# SparkFun_Breadboard_Power_Supply_5_3_3V.net
KiCad netlist of a schematic drawn in EAGLE
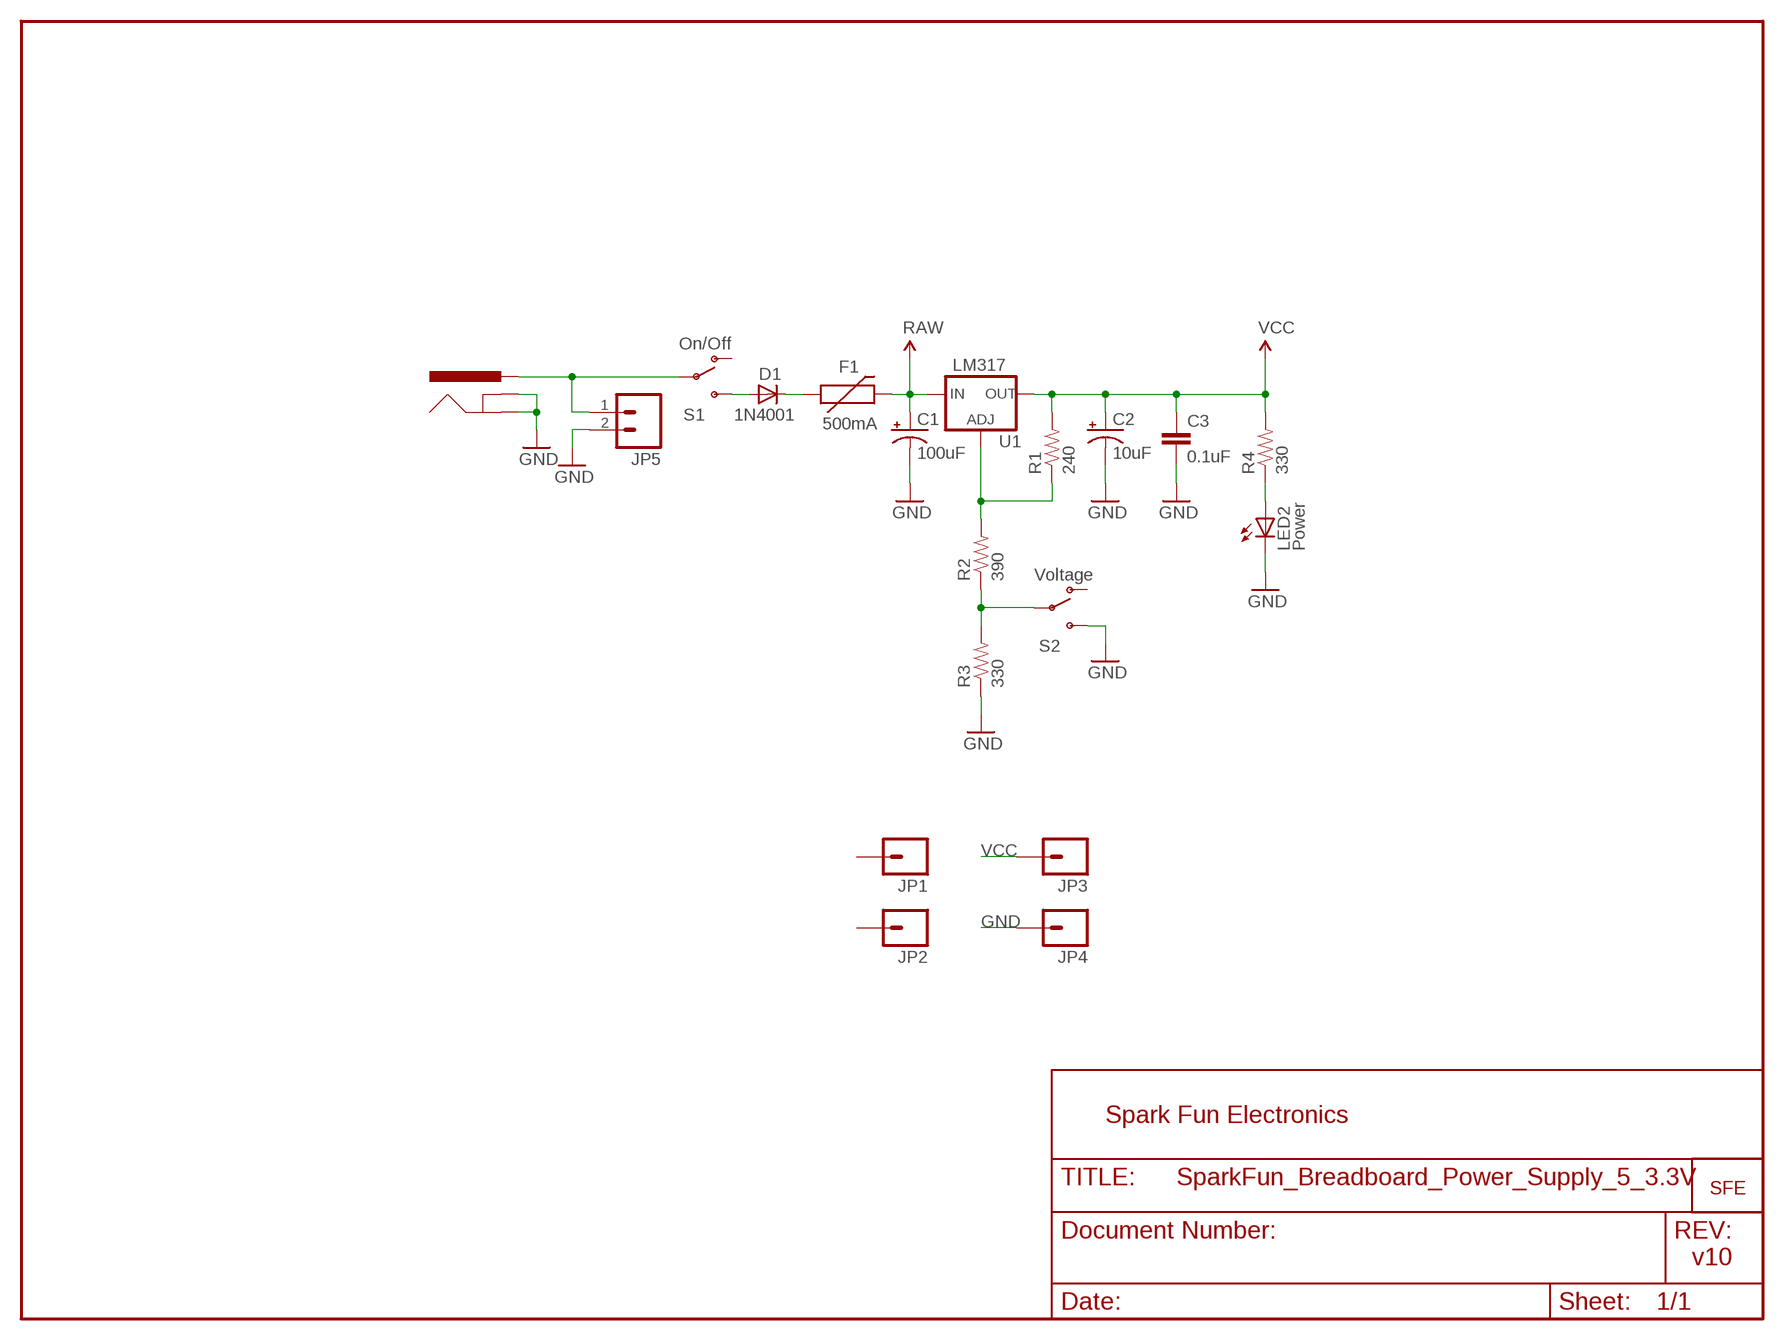
[diagram p0: schematic, sheet 1]

(export (version "E")
  (design (tool "Eeschema 10.0.6"))
  (components
    (comp (ref "C1")
      (value "100uF")
      (footprint "eagle-import:CPOL-RADIAL-100UF-25V")
      (libsource (lib "eagle-import") (part "CAP_POLPTH1"))
    )
    (comp (ref "C2")
      (value "10uF")
      (footprint "eagle-import:CPOL-RADIAL-10UF-25V")
      (libsource (lib "eagle-import") (part "CAP_POLPTH2"))
    )
    (comp (ref "C3")
      (value "0.1uF")
      (footprint "eagle-import:CAP-PTH-SMALL2")
      (libsource (lib "eagle-import") (part "CAPPTH2"))
    )
    (comp (ref "D1")
      (value "1N4001")
      (footprint "eagle-import:DIODE-0.4")
      (libsource (lib "eagle-import") (part "DIODEPTH"))
    )
    (comp (ref "F1")
      (value "500mA")
      (footprint "eagle-import:PTC")
      (libsource (lib "eagle-import") (part "PTCPTH"))
    )
    (comp (ref "J1")
      (value "POWER_JACKPTH")
      (footprint "eagle-import:POWER_JACK_PTH")
      (libsource (lib "eagle-import") (part "POWER_JACKPTH"))
    )
    (comp (ref "JP1")
      (value "M01PTH")
      (footprint "eagle-import:1X01")
      (libsource (lib "eagle-import") (part "M01PTH"))
    )
    (comp (ref "JP2")
      (value "M01PTH")
      (footprint "eagle-import:1X01")
      (libsource (lib "eagle-import") (part "M01PTH"))
    )
    (comp (ref "JP3")
      (value "M01PTH")
      (footprint "eagle-import:1X01")
      (libsource (lib "eagle-import") (part "M01PTH"))
    )
    (comp (ref "JP4")
      (value "M01PTH")
      (footprint "eagle-import:1X01")
      (libsource (lib "eagle-import") (part "M01PTH"))
    )
    (comp (ref "JP5")
      (value "M02PTH")
      (footprint "eagle-import:1X02")
      (libsource (lib "eagle-import") (part "M02PTH"))
    )
    (comp (ref "LED2")
      (value "Power")
      (footprint "eagle-import:LED5MM")
      (libsource (lib "eagle-import") (part "LED5MM"))
    )
    (comp (ref "R1")
      (value "240")
      (footprint "eagle-import:AXIAL-0.3")
      (libsource (lib "eagle-import") (part "RESISTORPTH1"))
    )
    (comp (ref "R2")
      (value "390")
      (footprint "eagle-import:AXIAL-0.3")
      (libsource (lib "eagle-import") (part "RESISTORPTH1"))
    )
    (comp (ref "R3")
      (value "330")
      (footprint "eagle-import:AXIAL-0.3")
      (libsource (lib "eagle-import") (part "RESISTORPTH1"))
    )
    (comp (ref "R4")
      (value "330")
      (footprint "eagle-import:AXIAL-0.3")
      (libsource (lib "eagle-import") (part "RESISTORPTH1"))
    )
    (comp (ref "S1")
      (value "On/Off")
      (footprint "eagle-import:SWITCH-SPST")
      (libsource (lib "eagle-import") (part "SWITCH-SPSTPTH"))
    )
    (comp (ref "S2")
      (value "Voltage")
      (footprint "eagle-import:SWITCH-SPST")
      (libsource (lib "eagle-import") (part "SWITCH-SPSTPTH"))
    )
    (comp (ref "U$1")
      (value "LOGO-SFESK")
      (footprint "eagle-import:SFE-LOGO-FLAME")
      (libsource (lib "eagle-import") (part "LOGO-SFESK"))
    )
    (comp (ref "U1")
      (value "LM317")
      (footprint "eagle-import:TO220-ADJ")
      (libsource (lib "eagle-import") (part "V_REG_317SINK"))
    )
  )
  (nets
    (net (code "1") (name "GND") (class "Default")
      (node (ref "C1") (pin "2") (pinfunction "-_2") (pintype "passive"))
      (node (ref "C2") (pin "2") (pinfunction "-_2") (pintype "passive"))
      (node (ref "C3") (pin "2") (pinfunction "2_2") (pintype "passive"))
      (node (ref "J1") (pin "GND") (pinfunction "GND_GND") (pintype "bidirectional"))
      (node (ref "J1") (pin "GNDBREAK") (pinfunction "GNDBREAK_GNDBREAK") (pintype "bidirectional"))
      (node (ref "JP4") (pin "1") (pinfunction "1_1") (pintype "passive"))
      (node (ref "JP5") (pin "2") (pinfunction "2_2") (pintype "passive"))
      (node (ref "LED2") (pin "K") (pinfunction "C_K") (pintype "passive"))
      (node (ref "R3") (pin "P$1") (pinfunction "1_P$1") (pintype "passive"))
      (node (ref "S2") (pin "3") (pinfunction "S_3") (pintype "passive"))
    )
    (net (code "2") (name "Net-(F1-1)") (class "Default")
      (node (ref "D1") (pin "C") (pinfunction "C_C") (pintype "passive"))
      (node (ref "F1") (pin "P$1") (pinfunction "1_P$1") (pintype "bidirectional"))
    )
    (net (code "3") (name "Net-(R1-1)") (class "Default")
      (node (ref "R1") (pin "P$1") (pinfunction "1_P$1") (pintype "passive"))
      (node (ref "R2") (pin "P$2") (pinfunction "2_P$2") (pintype "passive"))
      (node (ref "U1") (pin "ADJ") (pinfunction "ADJ_ADJ") (pintype "input"))
    )
    (net (code "4") (name "Net-(R2-1)") (class "Default")
      (node (ref "R2") (pin "P$1") (pinfunction "1_P$1") (pintype "passive"))
      (node (ref "R3") (pin "P$2") (pinfunction "2_P$2") (pintype "passive"))
      (node (ref "S2") (pin "2") (pinfunction "P_2") (pintype "passive"))
    )
    (net (code "5") (name "Net-(R4-1)") (class "Default")
      (node (ref "LED2") (pin "A") (pinfunction "A_A") (pintype "passive"))
      (node (ref "R4") (pin "P$1") (pinfunction "1_P$1") (pintype "passive"))
    )
    (net (code "6") (name "Net-(S1-P)") (class "Default")
      (node (ref "J1") (pin "PWR") (pinfunction "PWR_PWR") (pintype "bidirectional"))
      (node (ref "JP5") (pin "1") (pinfunction "1_1") (pintype "passive"))
      (node (ref "S1") (pin "2") (pinfunction "P_2") (pintype "passive"))
    )
    (net (code "7") (name "Net-(S1-S)") (class "Default")
      (node (ref "D1") (pin "A") (pinfunction "A_A") (pintype "passive"))
      (node (ref "S1") (pin "3") (pinfunction "S_3") (pintype "passive"))
    )
    (net (code "8") (name "RAW") (class "Default")
      (node (ref "C1") (pin "1") (pinfunction "+_1") (pintype "passive"))
      (node (ref "F1") (pin "P$2") (pinfunction "2_P$2") (pintype "bidirectional"))
      (node (ref "U1") (pin "IN") (pinfunction "IN_IN") (pintype "input"))
    )
    (net (code "9") (name "VCC") (class "Default")
      (node (ref "C2") (pin "1") (pinfunction "+_1") (pintype "passive"))
      (node (ref "C3") (pin "1") (pinfunction "1_1") (pintype "passive"))
      (node (ref "JP3") (pin "1") (pinfunction "1_1") (pintype "passive"))
      (node (ref "R1") (pin "P$2") (pinfunction "2_P$2") (pintype "passive"))
      (node (ref "R4") (pin "P$2") (pinfunction "2_P$2") (pintype "passive"))
      (node (ref "U1") (pin "OUT") (pinfunction "OUT_OUT") (pintype "output"))
    )
    (net (code "10") (name "unconnected-(JP1-Pad1)") (class "Default")
      (node (ref "JP1") (pin "1") (pinfunction "1_1") (pintype "passive"))
    )
    (net (code "11") (name "unconnected-(JP2-Pad1)") (class "Default")
      (node (ref "JP2") (pin "1") (pinfunction "1_1") (pintype "passive"))
    )
    (net (code "12") (name "unconnected-(S1-O-Pad1)") (class "Default")
      (node (ref "S1") (pin "1") (pinfunction "O_1") (pintype "passive"))
    )
    (net (code "13") (name "unconnected-(S2-O-Pad1)") (class "Default")
      (node (ref "S2") (pin "1") (pinfunction "O_1") (pintype "passive"))
    )
  )
)
